# design.net
KiCad netlist of a schematic drawn in Altium Designer
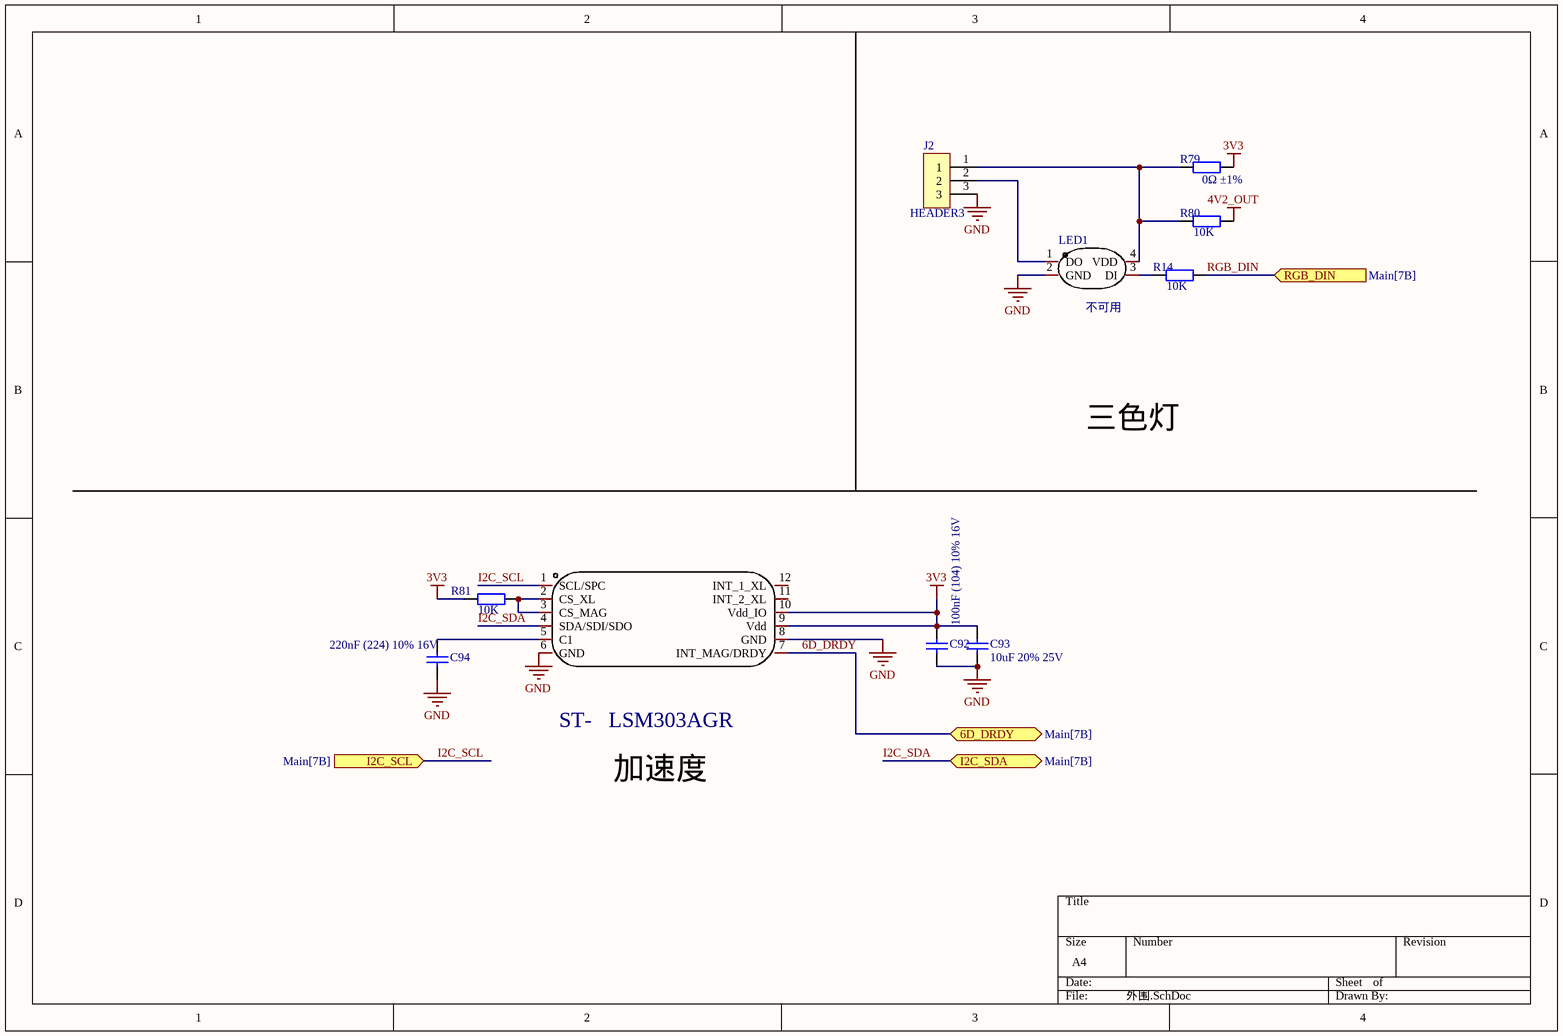
[diagram p0: 外围.SchDoc]

(export (version "E")
  (design (tool "Eeschema 10.0.6"))
  (components
    (comp (ref "C92")
      (value "100nF (104) 10% 16V")
      (footprint "0402_C")
      (description "贴片电容")
      (libsource (lib "Cap") (part "0402 100nF (104) 10% 16V"))
    )
    (comp (ref "C93")
      (value "10uF 20% 25V")
      (footprint "0402_C")
      (description "贴片电容")
      (libsource (lib "Cap") (part "0402 10uF (106) 20% 6.3V"))
    )
    (comp (ref "C94")
      (value "220nF (224) 10% 16V")
      (footprint "0201_C")
      (description "贴片电容")
      (libsource (lib "Cap") (part "0402 220nF (224) 10% 16V"))
    )
    (comp (ref "J2") (value "HEADER3") (footprint "HEADER3") (libsource (lib "RFID") (part "HEADER3")))
    (comp (ref "LED1")
      (value "WS2812B-2020")
      (footprint "LED-SMD_4P-L2.0-W2.0-TL_WS2812B-2020")
      (description "发光颜色:RGB三色;二极管配置:-;功率:-;透镜颜色:-;主波长:470.4nm；622.5nm；515.6nm;色温:-;发光角度:-;安装方式:-;工作温度:-;")
      (fields (field (name "MANUFACTURER") "worldsemi"))
      (libsource (lib "altium-import") (part "root_0_WS2812B-2020_"))
    )
    (comp (ref "R14")
      (value "10K")
      (footprint "0402_R")
      (description "Resistor")
      (libsource (lib "RFID") (part "Res2"))
    )
    (comp (ref "R79")
      (value "0Ω ±1%")
      (footprint "0402_R")
      (description "Resistor")
      (libsource (lib "RFID") (part "Res2"))
    )
    (comp (ref "R80")
      (value "10K")
      (footprint "0402_R")
      (description "Resistor")
      (fields (field (name "Comment") "NC"))
      (libsource (lib "RFID") (part "Res2"))
    )
    (comp (ref "R81")
      (value "10K")
      (footprint "0201_R")
      (description "Resistor")
      (libsource (lib "RFID") (part "Res2"))
    )
    (comp (ref "U15")
      (value "LSM303AGRTR")
      (footprint "LGA-12_L2.0-W2.0-P0.50-BL")
      (fields (field (name "MANUFACTURER") "ST(意法半导体)"))
      (libsource (lib "altium-import") (part "root_0_LSM303AGRTR_"))
    )
  )
  (nets
    (net (code "1") (name "/6D_DRDY") (class "Default")
      (node (ref "U15") (pin "7") (pinfunction "INT_MAG/DRDY_7") (pintype "passive"))
    )
    (net (code "2") (name "/I2C_SCL") (class "Default")
      (node (ref "U15") (pin "1") (pinfunction "SCL/SPC_1") (pintype "passive"))
    )
    (net (code "3") (name "/I2C_SDA") (class "Default")
      (node (ref "U15") (pin "4") (pinfunction "SDA/SDI/SDO_4") (pintype "passive"))
    )
    (net (code "4") (name "/RGB_DIN") (class "Default")
      (node (ref "R14") (pin "2") (pinfunction "2_2") (pintype "passive"))
    )
    (net (code "5") (name "3V3") (class "Default")
      (node (ref "C92") (pin "2") (pinfunction "2_2") (pintype "passive"))
      (node (ref "C93") (pin "2") (pinfunction "2_2") (pintype "passive"))
      (node (ref "R79") (pin "2") (pinfunction "2_2") (pintype "passive"))
      (node (ref "R81") (pin "1") (pinfunction "1_1") (pintype "passive"))
      (node (ref "U15") (pin "10") (pinfunction "Vdd_IO_10") (pintype "passive"))
      (node (ref "U15") (pin "9") (pinfunction "Vdd_9") (pintype "passive"))
    )
    (net (code "6") (name "4V2_OUT") (class "Default")
      (node (ref "R80") (pin "2") (pinfunction "2_2") (pintype "passive"))
    )
    (net (code "7") (name "GND") (class "Default")
      (node (ref "C92") (pin "1") (pinfunction "1_1") (pintype "passive"))
      (node (ref "C93") (pin "1") (pinfunction "1_1") (pintype "passive"))
      (node (ref "C94") (pin "1") (pinfunction "1_1") (pintype "passive"))
      (node (ref "J2") (pin "3") (pinfunction "3_3") (pintype "power_in"))
      (node (ref "LED1") (pin "2") (pinfunction "GND_2") (pintype "passive"))
      (node (ref "U15") (pin "6") (pinfunction "GND_6") (pintype "passive"))
      (node (ref "U15") (pin "8") (pinfunction "GND_8") (pintype "passive"))
    )
    (net (code "8") (name "Net-(LED1-DI)") (class "Default")
      (node (ref "LED1") (pin "3") (pinfunction "DI_3") (pintype "passive"))
      (node (ref "R14") (pin "1") (pinfunction "1_1") (pintype "passive"))
    )
    (net (code "9") (name "Net-(LED1-DO)") (class "Default")
      (node (ref "J2") (pin "2") (pinfunction "2_2") (pintype "power_in"))
      (node (ref "LED1") (pin "1") (pinfunction "DO_1") (pintype "passive"))
    )
    (net (code "10") (name "Net-(LED1-VDD)") (class "Default")
      (node (ref "J2") (pin "1") (pinfunction "1_1") (pintype "power_in"))
      (node (ref "LED1") (pin "4") (pinfunction "VDD_4") (pintype "passive"))
      (node (ref "R79") (pin "1") (pinfunction "1_1") (pintype "passive"))
      (node (ref "R80") (pin "1") (pinfunction "1_1") (pintype "passive"))
    )
    (net (code "11") (name "Net-(U15-C1)") (class "Default")
      (node (ref "C94") (pin "2") (pinfunction "2_2") (pintype "passive"))
      (node (ref "U15") (pin "5") (pinfunction "C1_5") (pintype "passive"))
    )
    (net (code "12") (name "Net-(U15-CS_MAG)") (class "Default")
      (node (ref "R81") (pin "2") (pinfunction "2_2") (pintype "passive"))
      (node (ref "U15") (pin "2") (pinfunction "CS_XL_2") (pintype "passive"))
      (node (ref "U15") (pin "3") (pinfunction "CS_MAG_3") (pintype "passive"))
    )
    (net (code "13") (name "unconnected-(U15-INT_1_XL-Pad12)") (class "Default")
      (node (ref "U15") (pin "12") (pinfunction "INT_1_XL_12") (pintype "passive"))
    )
    (net (code "14") (name "unconnected-(U15-INT_2_XL-Pad11)") (class "Default")
      (node (ref "U15") (pin "11") (pinfunction "INT_2_XL_11") (pintype "passive"))
    )
  )
)
